# MultiPSU.net
KiCad netlist of a schematic drawn in EAGLE
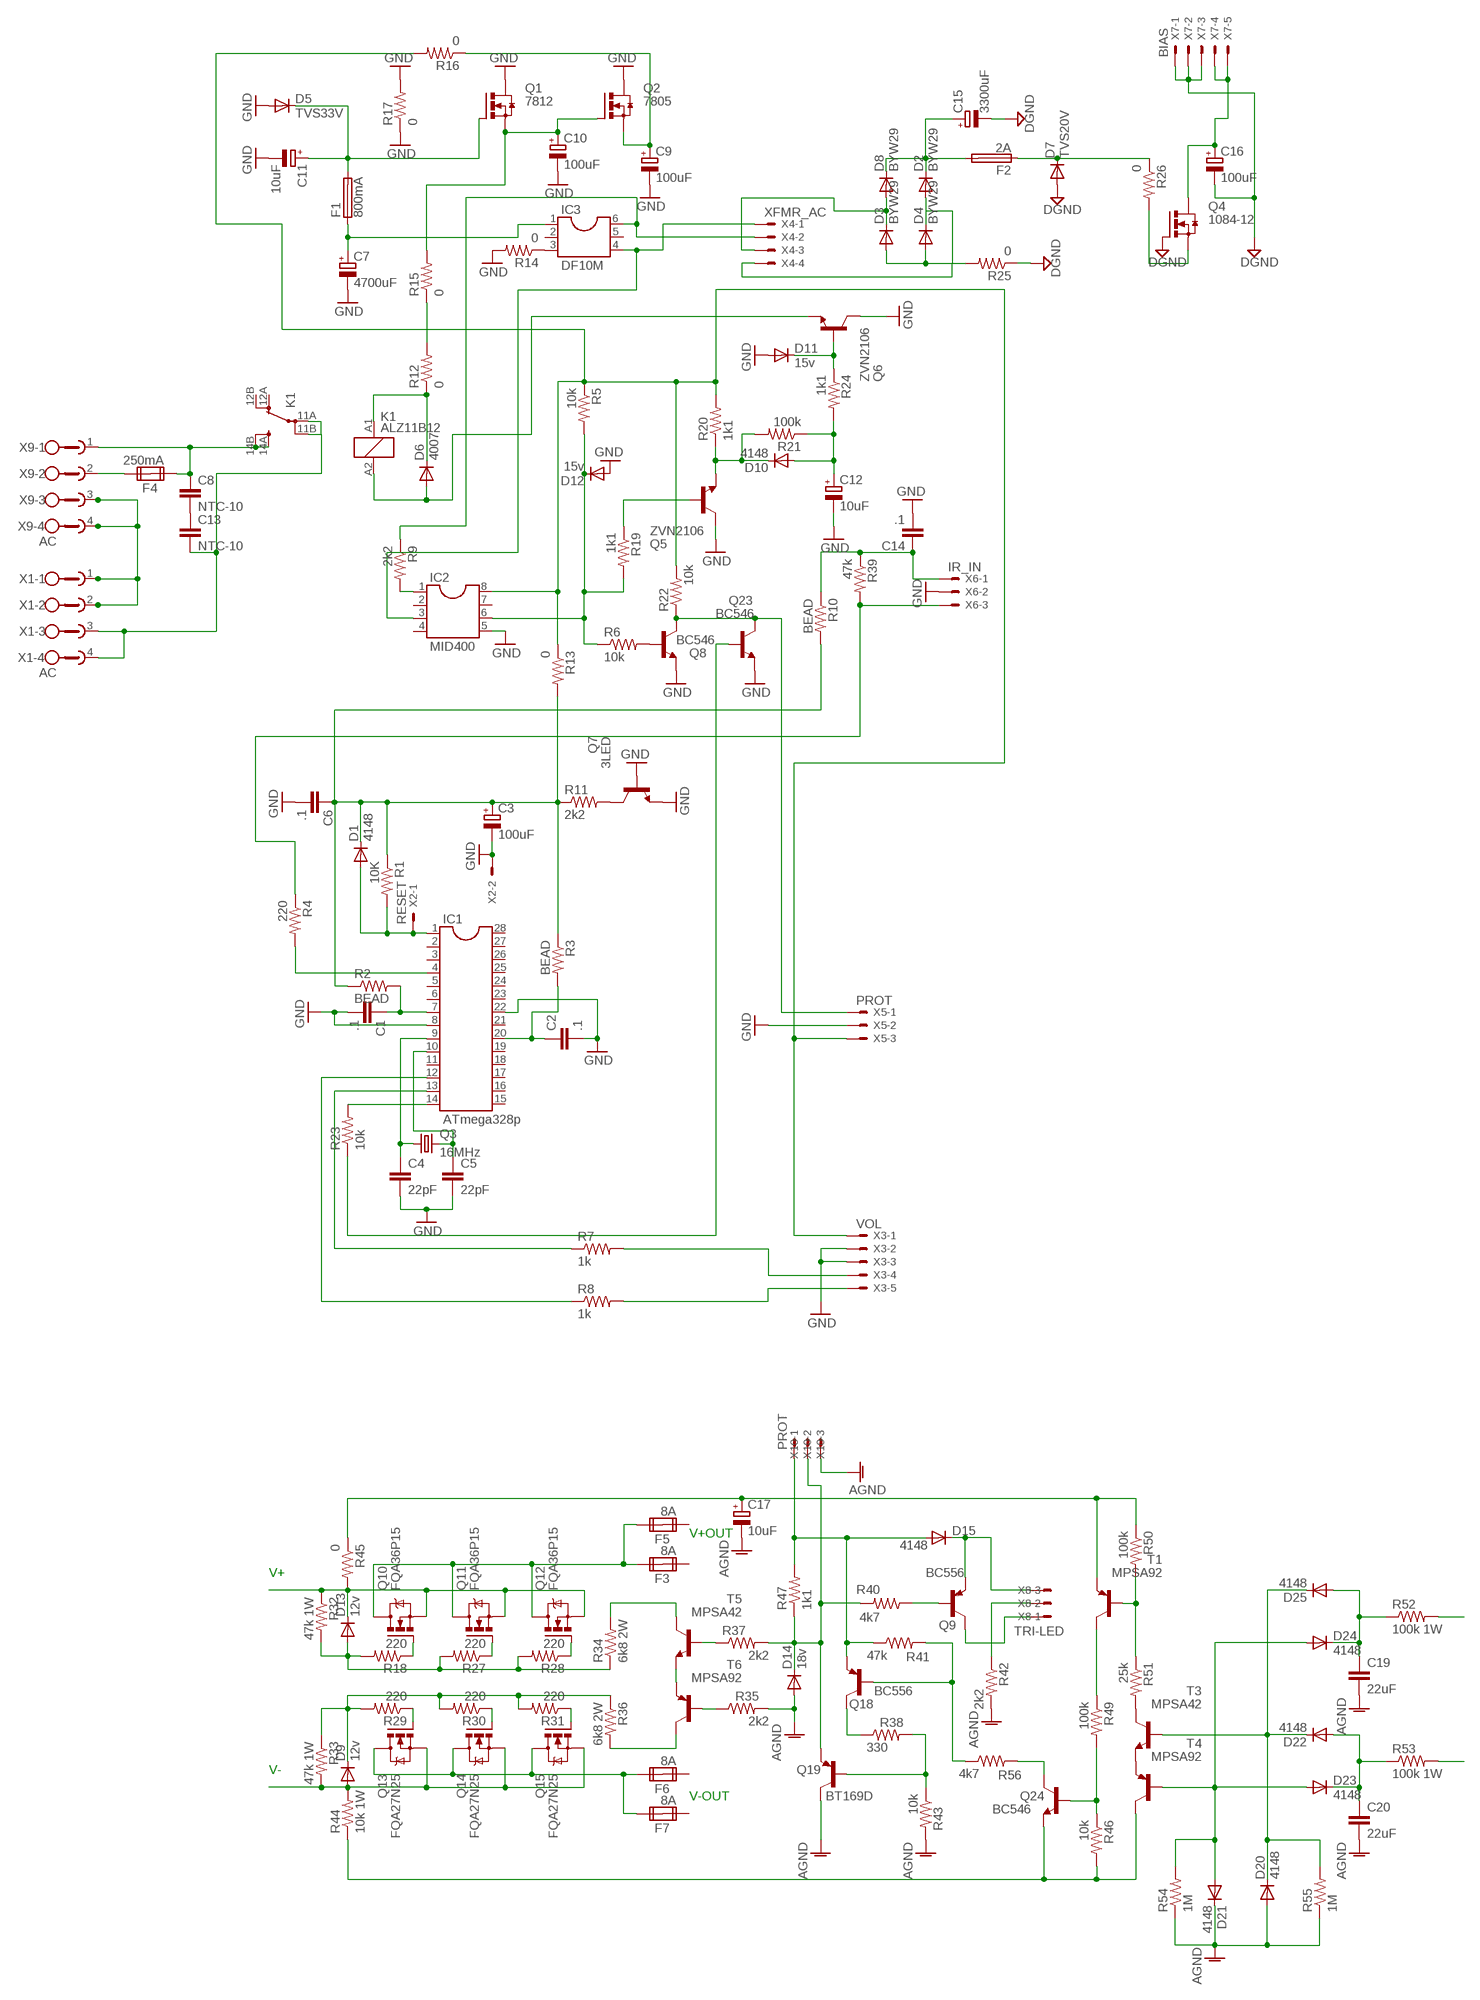
[diagram p0: schematic, sheet 1]

(export (version "E")
  (design (tool "Eeschema 10.0.6"))
  (components
    (comp (ref "C1")
      (value ".1")
      (footprint "eagle-import:C1210K")
      (libsource (lib "eagle-import") (part "C-EUC1210K"))
    )
    (comp (ref "C2")
      (value ".1")
      (footprint "eagle-import:C1210K")
      (libsource (lib "eagle-import") (part "C-EUC1210K"))
    )
    (comp (ref "C3")
      (value "100uF")
      (footprint "eagle-import:E3,5-10")
      (libsource (lib "eagle-import") (part "CPOL-EUE3.5-10"))
    )
    (comp (ref "C4")
      (value "22pF")
      (footprint "eagle-import:C1210K")
      (libsource (lib "eagle-import") (part "C-EUC1210K"))
    )
    (comp (ref "C5")
      (value "22pF")
      (footprint "eagle-import:C1210K")
      (libsource (lib "eagle-import") (part "C-EUC1210K"))
    )
    (comp (ref "C6")
      (value ".1")
      (footprint "eagle-import:C1210K")
      (libsource (lib "eagle-import") (part "C-EUC1210K"))
    )
    (comp (ref "C7")
      (value "4700uF")
      (footprint "eagle-import:E7,5-16")
      (libsource (lib "eagle-import") (part "CPOL-EUE7.5-16"))
    )
    (comp (ref "C8")
      (value "NTC-10")
      (footprint "eagle-import:C102-054X133")
      (libsource (lib "eagle-import") (part "C-EU102-054X133"))
    )
    (comp (ref "C9")
      (value "100uF")
      (footprint "eagle-import:E3,5-10")
      (libsource (lib "eagle-import") (part "CPOL-EUE3.5-10"))
    )
    (comp (ref "C10")
      (value "100uF")
      (footprint "eagle-import:E3,5-10")
      (libsource (lib "eagle-import") (part "CPOL-EUE3.5-10"))
    )
    (comp (ref "C11")
      (value "10uF")
      (footprint "eagle-import:E3,5-10")
      (libsource (lib "eagle-import") (part "CPOL-EUE3.5-10"))
    )
    (comp (ref "C12")
      (value "10uF")
      (footprint "eagle-import:E3,5-10")
      (libsource (lib "eagle-import") (part "CPOL-EUE3.5-10"))
    )
    (comp (ref "C13")
      (value "NTC-10")
      (footprint "eagle-import:C102-054X133")
      (libsource (lib "eagle-import") (part "C-EU102-054X133"))
    )
    (comp (ref "C14")
      (value ".1")
      (footprint "eagle-import:C1210K")
      (libsource (lib "eagle-import") (part "C-EUC1210K"))
    )
    (comp (ref "C15")
      (value "3300uF")
      (footprint "eagle-import:E7,5-16")
      (libsource (lib "eagle-import") (part "CPOL-EUE7.5-16"))
    )
    (comp (ref "C16")
      (value "100uF")
      (footprint "eagle-import:E3,5-10")
      (libsource (lib "eagle-import") (part "CPOL-EUE3.5-10"))
    )
    (comp (ref "C17")
      (value "10uF")
      (footprint "eagle-import:E3,5-10")
      (libsource (lib "eagle-import") (part "CPOL-EUE3.5-10"))
    )
    (comp (ref "C19")
      (value "22uF")
      (footprint "eagle-import:C050-075X075")
      (libsource (lib "eagle-import") (part "C-EU050-075X075"))
    )
    (comp (ref "C20")
      (value "22uF")
      (footprint "eagle-import:C050-075X075")
      (libsource (lib "eagle-import") (part "C-EU050-075X075"))
    )
    (comp (ref "D1")
      (value "4148")
      (footprint "eagle-import:DO35-7")
      (libsource (lib "eagle-import") (part "1N4148DO35-7"))
    )
    (comp (ref "D2")
      (value "BYW29")
      (footprint "eagle-import:DO220S")
      (libsource (lib "eagle-import") (part "BYW29"))
    )
    (comp (ref "D3")
      (value "BYW29")
      (footprint "eagle-import:DO220S")
      (libsource (lib "eagle-import") (part "BYW29"))
    )
    (comp (ref "D4")
      (value "BYW29")
      (footprint "eagle-import:DO220S")
      (libsource (lib "eagle-import") (part "BYW29"))
    )
    (comp (ref "D5")
      (value "TVS33V")
      (footprint "eagle-import:SOD57-10")
      (libsource (lib "eagle-import") (part "BY448"))
    )
    (comp (ref "D6")
      (value "4007")
      (footprint "eagle-import:DO41-10")
      (libsource (lib "eagle-import") (part "1N4004"))
    )
    (comp (ref "D7")
      (value "TVS20V")
      (footprint "eagle-import:SOD57-10")
      (libsource (lib "eagle-import") (part "BY448"))
    )
    (comp (ref "D8")
      (value "BYW29")
      (footprint "eagle-import:DO220S")
      (libsource (lib "eagle-import") (part "BYW29"))
    )
    (comp (ref "D9")
      (value "12v")
      (footprint "eagle-import:DO41-10")
      (libsource (lib "eagle-import") (part "1N4004"))
    )
    (comp (ref "D10")
      (value "4148")
      (footprint "eagle-import:DO35-10")
      (libsource (lib "eagle-import") (part "1N4148DO35-10"))
    )
    (comp (ref "D11")
      (value "15v")
      (footprint "eagle-import:DO35-7")
      (libsource (lib "eagle-import") (part "1N4148DO35-7"))
    )
    (comp (ref "D12")
      (value "15v")
      (footprint "eagle-import:DO35-7")
      (libsource (lib "eagle-import") (part "1N4148DO35-7"))
    )
    (comp (ref "D13")
      (value "12v")
      (footprint "eagle-import:DO41-10")
      (libsource (lib "eagle-import") (part "1N4004"))
    )
    (comp (ref "D14")
      (value "18v")
      (footprint "eagle-import:DO41-10")
      (libsource (lib "eagle-import") (part "1N4004"))
    )
    (comp (ref "D15")
      (value "4148")
      (footprint "eagle-import:DO41-10")
      (libsource (lib "eagle-import") (part "1N4004"))
    )
    (comp (ref "D20")
      (value "4148")
      (footprint "eagle-import:DO35-7")
      (libsource (lib "eagle-import") (part "1N4148DO35-7"))
    )
    (comp (ref "D21")
      (value "4148")
      (footprint "eagle-import:DO35-7")
      (libsource (lib "eagle-import") (part "1N4148DO35-7"))
    )
    (comp (ref "D22")
      (value "4148")
      (footprint "eagle-import:DO35-7")
      (libsource (lib "eagle-import") (part "1N4148DO35-7"))
    )
    (comp (ref "D23")
      (value "4148")
      (footprint "eagle-import:DO35-7")
      (libsource (lib "eagle-import") (part "1N4148DO35-7"))
    )
    (comp (ref "D24")
      (value "4148")
      (footprint "eagle-import:DO35-7")
      (libsource (lib "eagle-import") (part "1N4148DO35-7"))
    )
    (comp (ref "D25")
      (value "4148")
      (footprint "eagle-import:DO35-7")
      (libsource (lib "eagle-import") (part "1N4148DO35-7"))
    )
    (comp (ref "F1")
      (value "800mA")
      (footprint "eagle-import:19560")
      (fields (field (name "MPN") "56000001009"))
      (libsource (lib "eagle-import") (part "19560"))
    )
    (comp (ref "F2")
      (value "2A")
      (footprint "eagle-import:19560")
      (fields (field (name "MPN") "56000001009"))
      (libsource (lib "eagle-import") (part "19560"))
    )
    (comp (ref "F3")
      (value "8A")
      (footprint "eagle-import:FUSE1")
      (libsource (lib "eagle-import") (part "FUSE2P"))
    )
    (comp (ref "F4")
      (value "250mA")
      (footprint "eagle-import:FUSE1")
      (libsource (lib "eagle-import") (part "FUSE2P"))
    )
    (comp (ref "F5")
      (value "8A")
      (footprint "eagle-import:FUSE1")
      (libsource (lib "eagle-import") (part "FUSE2P"))
    )
    (comp (ref "F6")
      (value "8A")
      (footprint "eagle-import:FUSE1")
      (libsource (lib "eagle-import") (part "FUSE2P"))
    )
    (comp (ref "F7")
      (value "8A")
      (footprint "eagle-import:FUSE1")
      (libsource (lib "eagle-import") (part "FUSE2P"))
    )
    (comp (ref "IC1")
      (value "ATmega328p")
      (footprint "eagle-import:DIL28-3")
      (libsource (lib "eagle-import") (part "DIL28-3"))
    )
    (comp (ref "IC2")
      (value "MID400")
      (footprint "eagle-import:DIL08")
      (libsource (lib "eagle-import") (part "DIL8"))
    )
    (comp (ref "IC3")
      (value "DF10M")
      (footprint "eagle-import:DIL06")
      (libsource (lib "eagle-import") (part "DIL6"))
    )
    (comp (ref "K1")
      (value "ALZ11B12")
      (footprint "eagle-import:RT-C_O16A5")
      (fields (field (name "MPN") "RT314730"))
      (libsource (lib "eagle-import") (part "RT314730"))
    )
    (comp (ref "Q1")
      (value "7812")
      (footprint "eagle-import:TO220BH")
      (libsource (lib "eagle-import") (part "IRFI540NPBF"))
    )
    (comp (ref "Q2")
      (value "7805")
      (footprint "eagle-import:TO220BH")
      (libsource (lib "eagle-import") (part "IRFI540NPBF"))
    )
    (comp (ref "Q3")
      (value "16MHz")
      (footprint "eagle-import:HC49_S")
      (libsource (lib "eagle-import") (part "CRYSTALHC49S"))
    )
    (comp (ref "Q4")
      (value "1084-12")
      (footprint "eagle-import:TO220BH")
      (libsource (lib "eagle-import") (part "IRFI540NPBF"))
    )
    (comp (ref "Q5")
      (value "ZVN2106")
      (footprint "eagle-import:TO92-EBC")
      (libsource (lib "eagle-import") (part "BC550B"))
    )
    (comp (ref "Q6")
      (value "ZVN2106")
      (footprint "eagle-import:TO92-EBC")
      (libsource (lib "eagle-import") (part "BC550B"))
    )
    (comp (ref "Q7")
      (value "3LED")
      (footprint "eagle-import:TO92-EBC")
      (libsource (lib "eagle-import") (part "BC546A"))
    )
    (comp (ref "Q8")
      (value "BC546")
      (footprint "eagle-import:TO92-EBC")
      (libsource (lib "eagle-import") (part "BC550B"))
    )
    (comp (ref "Q9")
      (value "BC556")
      (footprint "eagle-import:TO92-EBC")
      (libsource (lib "eagle-import") (part "BC560"))
    )
    (comp (ref "Q10")
      (value "FQA36P15")
      (footprint "eagle-import:TO-247AD-H")
      (libsource (lib "eagle-import") (part "IXF?6NH_100"))
    )
    (comp (ref "Q11")
      (value "FQA36P15")
      (footprint "eagle-import:TO-247AD-H")
      (libsource (lib "eagle-import") (part "IXF?6NH_100"))
    )
    (comp (ref "Q12")
      (value "FQA36P15")
      (footprint "eagle-import:TO-247AD-H")
      (libsource (lib "eagle-import") (part "IXF?6NH_100"))
    )
    (comp (ref "Q13")
      (value "FQA27N25")
      (footprint "eagle-import:TO-247AD-H")
      (libsource (lib "eagle-import") (part "IXF?6NH_100"))
    )
    (comp (ref "Q14")
      (value "FQA27N25")
      (footprint "eagle-import:TO-247AD-H")
      (libsource (lib "eagle-import") (part "IXF?6NH_100"))
    )
    (comp (ref "Q15")
      (value "FQA27N25")
      (footprint "eagle-import:TO-247AD-H")
      (libsource (lib "eagle-import") (part "IXF?6NH_100"))
    )
    (comp (ref "Q18")
      (value "BC556")
      (footprint "eagle-import:TO92-EBC")
      (libsource (lib "eagle-import") (part "BC560"))
    )
    (comp (ref "Q19")
      (value "BT169D")
      (footprint "eagle-import:TO92-EBC")
      (libsource (lib "eagle-import") (part "BC560"))
    )
    (comp (ref "Q23")
      (value "BC546")
      (footprint "eagle-import:TO92-EBC")
      (libsource (lib "eagle-import") (part "BC550B"))
    )
    (comp (ref "Q24")
      (value "BC546")
      (footprint "eagle-import:TO92-EBC")
      (libsource (lib "eagle-import") (part "BC550B"))
    )
    (comp (ref "R1")
      (value "10K")
      (footprint "eagle-import:0309_10")
      (libsource (lib "eagle-import") (part "R-US_0309/10"))
    )
    (comp (ref "R2")
      (value "BEAD")
      (footprint "eagle-import:0309_10")
      (libsource (lib "eagle-import") (part "R-US_0309/10"))
    )
    (comp (ref "R3")
      (value "BEAD")
      (footprint "eagle-import:0309_12")
      (libsource (lib "eagle-import") (part "R-US_0309/12"))
    )
    (comp (ref "R4")
      (value "220")
      (footprint "eagle-import:0309_12")
      (libsource (lib "eagle-import") (part "R-US_0309/12"))
    )
    (comp (ref "R5")
      (value "10k")
      (footprint "eagle-import:0309_10")
      (libsource (lib "eagle-import") (part "R-US_0309/10"))
    )
    (comp (ref "R6")
      (value "10k")
      (footprint "eagle-import:0309_12")
      (libsource (lib "eagle-import") (part "R-US_0309/12"))
    )
    (comp (ref "R7")
      (value "1k")
      (footprint "eagle-import:R1210")
      (libsource (lib "eagle-import") (part "R-US_R1210"))
    )
    (comp (ref "R8")
      (value "1k")
      (footprint "eagle-import:R1210")
      (libsource (lib "eagle-import") (part "R-US_R1210"))
    )
    (comp (ref "R9")
      (value "2k2")
      (footprint "eagle-import:0309_12")
      (libsource (lib "eagle-import") (part "R-US_0309/12"))
    )
    (comp (ref "R10")
      (value "BEAD")
      (footprint "eagle-import:0309_10")
      (libsource (lib "eagle-import") (part "R-US_0309/10"))
    )
    (comp (ref "R11")
      (value "2k2")
      (footprint "eagle-import:0309_10")
      (libsource (lib "eagle-import") (part "R-US_0309/10"))
    )
    (comp (ref "R12")
      (value "0")
      (footprint "eagle-import:0309_10")
      (libsource (lib "eagle-import") (part "R-US_0309/10"))
    )
    (comp (ref "R13")
      (value "0")
      (footprint "eagle-import:0309_12")
      (libsource (lib "eagle-import") (part "R-US_0309/12"))
    )
    (comp (ref "R14")
      (value "0")
      (footprint "eagle-import:0309_10")
      (libsource (lib "eagle-import") (part "R-US_0309/10"))
    )
    (comp (ref "R15")
      (value "0")
      (footprint "eagle-import:0309_12")
      (libsource (lib "eagle-import") (part "R-US_0309/12"))
    )
    (comp (ref "R16")
      (value "0")
      (footprint "eagle-import:0309_12")
      (libsource (lib "eagle-import") (part "R-US_0309/12"))
    )
    (comp (ref "R17")
      (value "0")
      (footprint "eagle-import:0309_12")
      (libsource (lib "eagle-import") (part "R-US_0309/12"))
    )
    (comp (ref "R18")
      (value "220")
      (footprint "eagle-import:0309_12")
      (libsource (lib "eagle-import") (part "R-US_0309/12"))
    )
    (comp (ref "R19")
      (value "1k1")
      (footprint "eagle-import:0309_12")
      (libsource (lib "eagle-import") (part "R-US_0309/12"))
    )
    (comp (ref "R20")
      (value "1k1")
      (footprint "eagle-import:0309_10")
      (libsource (lib "eagle-import") (part "R-US_0309/10"))
    )
    (comp (ref "R21")
      (value "100k")
      (footprint "eagle-import:0309_10")
      (libsource (lib "eagle-import") (part "R-US_0309/10"))
    )
    (comp (ref "R22")
      (value "10k")
      (footprint "eagle-import:0309_10")
      (libsource (lib "eagle-import") (part "R-US_0309/10"))
    )
    (comp (ref "R23")
      (value "10k")
      (footprint "eagle-import:R1210")
      (libsource (lib "eagle-import") (part "R-US_R1210"))
    )
    (comp (ref "R24")
      (value "1k1")
      (footprint "eagle-import:0309_10")
      (libsource (lib "eagle-import") (part "R-US_0309/10"))
    )
    (comp (ref "R25")
      (value "0")
      (footprint "eagle-import:0309_12")
      (libsource (lib "eagle-import") (part "R-US_0309/12"))
    )
    (comp (ref "R26")
      (value "0")
      (footprint "eagle-import:0309_12")
      (libsource (lib "eagle-import") (part "R-US_0309/12"))
    )
    (comp (ref "R27")
      (value "220")
      (footprint "eagle-import:0309_12")
      (libsource (lib "eagle-import") (part "R-US_0309/12"))
    )
    (comp (ref "R28")
      (value "220")
      (footprint "eagle-import:0309_12")
      (libsource (lib "eagle-import") (part "R-US_0309/12"))
    )
    (comp (ref "R29")
      (value "220")
      (footprint "eagle-import:0309_12")
      (libsource (lib "eagle-import") (part "R-US_0309/12"))
    )
    (comp (ref "R30")
      (value "220")
      (footprint "eagle-import:0309_12")
      (libsource (lib "eagle-import") (part "R-US_0309/12"))
    )
    (comp (ref "R31")
      (value "220")
      (footprint "eagle-import:0309_12")
      (libsource (lib "eagle-import") (part "R-US_0309/12"))
    )
    (comp (ref "R32")
      (value "47k 1W")
      (footprint "eagle-import:0411_15")
      (libsource (lib "eagle-import") (part "R-US_0411/15"))
    )
    (comp (ref "R33")
      (value "47k 1W")
      (footprint "eagle-import:0411_15")
      (libsource (lib "eagle-import") (part "R-US_0411/15"))
    )
    (comp (ref "R34")
      (value "6k8 2W")
      (footprint "eagle-import:0411_15")
      (libsource (lib "eagle-import") (part "R-US_0411/15"))
    )
    (comp (ref "R35")
      (value "2k2")
      (footprint "eagle-import:0309_10")
      (libsource (lib "eagle-import") (part "R-US_0309/10"))
    )
    (comp (ref "R36")
      (value "6k8 2W")
      (footprint "eagle-import:0411_15")
      (libsource (lib "eagle-import") (part "R-US_0411/15"))
    )
    (comp (ref "R37")
      (value "2k2")
      (footprint "eagle-import:0309_10")
      (libsource (lib "eagle-import") (part "R-US_0309/10"))
    )
    (comp (ref "R38")
      (value "330")
      (footprint "eagle-import:0309_10")
      (libsource (lib "eagle-import") (part "R-US_0309/10"))
    )
    (comp (ref "R39")
      (value "47k")
      (footprint "eagle-import:0309_10")
      (libsource (lib "eagle-import") (part "R-US_0309/10"))
    )
    (comp (ref "R40")
      (value "4k7")
      (footprint "eagle-import:0309_10")
      (libsource (lib "eagle-import") (part "R-US_0309/10"))
    )
    (comp (ref "R41")
      (value "47k")
      (footprint "eagle-import:0309_10")
      (libsource (lib "eagle-import") (part "R-US_0309/10"))
    )
    (comp (ref "R42")
      (value "2k2")
      (footprint "eagle-import:0309_10")
      (libsource (lib "eagle-import") (part "R-US_0309/10"))
    )
    (comp (ref "R43")
      (value "10k")
      (footprint "eagle-import:0309_10")
      (libsource (lib "eagle-import") (part "R-US_0309/10"))
    )
    (comp (ref "R44")
      (value "10k 1W")
      (footprint "eagle-import:0411_15")
      (libsource (lib "eagle-import") (part "R-US_0411/15"))
    )
    (comp (ref "R45")
      (value "0")
      (footprint "eagle-import:0309_12")
      (libsource (lib "eagle-import") (part "R-US_0309/12"))
    )
    (comp (ref "R46")
      (value "10k")
      (footprint "eagle-import:0411_15")
      (libsource (lib "eagle-import") (part "R-US_0411/15"))
    )
    (comp (ref "R47")
      (value "1k1")
      (footprint "eagle-import:0309_10")
      (libsource (lib "eagle-import") (part "R-US_0309/10"))
    )
    (comp (ref "R49")
      (value "100k")
      (footprint "eagle-import:0411_15")
      (libsource (lib "eagle-import") (part "R-US_0411/15"))
    )
    (comp (ref "R50")
      (value "100k")
      (footprint "eagle-import:0309_10")
      (libsource (lib "eagle-import") (part "R-US_0309/10"))
    )
    (comp (ref "R51")
      (value "25k")
      (footprint "eagle-import:0309_10")
      (libsource (lib "eagle-import") (part "R-US_0309/10"))
    )
    (comp (ref "R52")
      (value "100k 1W")
      (footprint "eagle-import:0309_10")
      (libsource (lib "eagle-import") (part "R-US_0309/10"))
    )
    (comp (ref "R53")
      (value "100k 1W")
      (footprint "eagle-import:0309_10")
      (libsource (lib "eagle-import") (part "R-US_0309/10"))
    )
    (comp (ref "R54")
      (value "1M")
      (footprint "eagle-import:R1210")
      (libsource (lib "eagle-import") (part "R-US_R1210"))
    )
    (comp (ref "R55")
      (value "1M")
      (footprint "eagle-import:R1210")
      (libsource (lib "eagle-import") (part "R-US_R1210"))
    )
    (comp (ref "R56")
      (value "4k7")
      (footprint "eagle-import:0309_10")
      (libsource (lib "eagle-import") (part "R-US_0309/10"))
    )
    (comp (ref "T1")
      (value "MPSA92")
      (footprint "eagle-import:TO92-EBC")
      (libsource (lib "eagle-import") (part "-PNP-TO92-EBCMPSA92"))
    )
    (comp (ref "T3")
      (value "MPSA42")
      (footprint "eagle-import:TO92-EBC")
      (libsource (lib "eagle-import") (part "-NPN-TO92-EBCMPSA42"))
    )
    (comp (ref "T4")
      (value "MPSA92")
      (footprint "eagle-import:TO92-EBC")
      (libsource (lib "eagle-import") (part "-PNP-TO92-EBCMPSA92"))
    )
    (comp (ref "T5")
      (value "MPSA42")
      (footprint "eagle-import:TO92-EBC")
      (libsource (lib "eagle-import") (part "-NPN-TO92-EBCMPSA42"))
    )
    (comp (ref "T6")
      (value "MPSA92")
      (footprint "eagle-import:TO92-EBC")
      (libsource (lib "eagle-import") (part "-PNP-TO92-EBCMPSA92"))
    )
    (comp (ref "X1")
      (value "AC")
      (footprint "eagle-import:GMSTBA4")
      (fields (field (name "MF") "FARNELL") (field (name "MPN") "1757268"))
      (libsource (lib "eagle-import") (part "GMSTBA4"))
    )
    (comp (ref "X2")
      (value "RESET")
      (footprint "eagle-import:22-23-2021")
      (fields (field (name "MF") "MOLEX") (field (name "MPN") "22-23-2021"))
      (libsource (lib "eagle-import") (part "22-23-2021"))
    )
    (comp (ref "X3")
      (value "VOL")
      (footprint "eagle-import:22-23-2051")
      (fields (field (name "MF") "MOLEX") (field (name "MPN") "22-23-2051"))
      (libsource (lib "eagle-import") (part "22-23-2051"))
    )
    (comp (ref "X4")
      (value "XFMR_AC")
      (footprint "eagle-import:5566-4")
      (libsource (lib "eagle-import") (part "5566-4"))
    )
    (comp (ref "X5")
      (value "PROT")
      (footprint "eagle-import:22-23-2031")
      (fields (field (name "MF") "MOLEX") (field (name "MPN") "22-23-2031"))
      (libsource (lib "eagle-import") (part "22-23-2031"))
    )
    (comp (ref "X6")
      (value "IR_IN")
      (footprint "eagle-import:22-23-2031")
      (fields (field (name "MF") "MOLEX") (field (name "MPN") "22-23-2031"))
      (libsource (lib "eagle-import") (part "22-23-2031"))
    )
    (comp (ref "X7")
      (value "BIAS")
      (footprint "eagle-import:22-23-2051")
      (fields (field (name "MF") "MOLEX") (field (name "MPN") "22-23-2051"))
      (libsource (lib "eagle-import") (part "22-23-2051"))
    )
    (comp (ref "X8")
      (value "TRI-LED")
      (footprint "eagle-import:22-23-2031")
      (fields (field (name "MF") "MOLEX") (field (name "MPN") "22-23-2031"))
      (libsource (lib "eagle-import") (part "22-23-2031"))
    )
    (comp (ref "X9")
      (value "AC")
      (footprint "eagle-import:GMSTBA4")
      (fields (field (name "MF") "FARNELL") (field (name "MPN") "1757268"))
      (libsource (lib "eagle-import") (part "GMSTBA4"))
    )
    (comp (ref "X10")
      (value "PROT")
      (footprint "eagle-import:22-23-2031")
      (fields (field (name "MF") "MOLEX") (field (name "MPN") "22-23-2031"))
      (libsource (lib "eagle-import") (part "22-23-2031"))
    )
  )
  (nets
    (net (code "1") (name "AGND") (class "Default")
      (node (ref "C17") (pin "-") (pinfunction "-_-") (pintype "passive"))
      (node (ref "C19") (pin "2") (pinfunction "2_2") (pintype "passive"))
      (node (ref "C20") (pin "2") (pinfunction "2_2") (pintype "passive"))
      (node (ref "D14") (pin "A") (pinfunction "A_A") (pintype "passive"))
      (node (ref "D20") (pin "A") (pinfunction "A_A") (pintype "passive"))
      (node (ref "D21") (pin "C") (pinfunction "C_C") (pintype "passive"))
      (node (ref "Q19") (pin "C") (pinfunction "C_C") (pintype "passive"))
      (node (ref "R35") (pin "2") (pinfunction "2_2") (pintype "passive"))
      (node (ref "R42") (pin "2") (pinfunction "2_2") (pintype "passive"))
      (node (ref "R43") (pin "2") (pinfunction "2_2") (pintype "passive"))
      (node (ref "R54") (pin "1") (pinfunction "1_1") (pintype "passive"))
      (node (ref "R55") (pin "1") (pinfunction "1_1") (pintype "passive"))
      (node (ref "X10") (pin "3") (pinfunction "S_3") (pintype "passive"))
    )
    (net (code "2") (name "DGND") (class "Default")
      (node (ref "C15") (pin "-") (pinfunction "-_-") (pintype "passive"))
      (node (ref "C16") (pin "-") (pinfunction "-_-") (pintype "passive"))
      (node (ref "D7") (pin "A") (pinfunction "A_A") (pintype "passive"))
      (node (ref "Q4") (pin "G") (pinfunction "G_G") (pintype "passive"))
      (node (ref "R25") (pin "1") (pinfunction "1_1") (pintype "passive"))
      (node (ref "X7") (pin "1") (pinfunction "S_1") (pintype "passive"))
      (node (ref "X7") (pin "2") (pinfunction "S_2") (pintype "passive"))
      (node (ref "X7") (pin "3") (pinfunction "S_3") (pintype "passive"))
    )
    (net (code "3") (name "GND") (class "Default")
      (node (ref "C1") (pin "2") (pinfunction "2_2") (pintype "passive"))
      (node (ref "C10") (pin "-") (pinfunction "-_-") (pintype "passive"))
      (node (ref "C11") (pin "-") (pinfunction "-_-") (pintype "passive"))
      (node (ref "C12") (pin "-") (pinfunction "-_-") (pintype "passive"))
      (node (ref "C14") (pin "2") (pinfunction "2_2") (pintype "passive"))
      (node (ref "C2") (pin "2") (pinfunction "2_2") (pintype "passive"))
      (node (ref "C3") (pin "-") (pinfunction "-_-") (pintype "passive"))
      (node (ref "C4") (pin "2") (pinfunction "2_2") (pintype "passive"))
      (node (ref "C5") (pin "2") (pinfunction "2_2") (pintype "passive"))
      (node (ref "C6") (pin "2") (pinfunction "2_2") (pintype "passive"))
      (node (ref "C7") (pin "-") (pinfunction "-_-") (pintype "passive"))
      (node (ref "C9") (pin "-") (pinfunction "-_-") (pintype "passive"))
      (node (ref "D11") (pin "A") (pinfunction "A_A") (pintype "passive"))
      (node (ref "D12") (pin "A") (pinfunction "A_A") (pintype "passive"))
      (node (ref "D5") (pin "A") (pinfunction "A_A") (pintype "passive"))
      (node (ref "IC1") (pin "22") (pinfunction "22_22") (pintype "passive"))
      (node (ref "IC1") (pin "8") (pinfunction "8_8") (pintype "passive"))
      (node (ref "IC2") (pin "5") (pinfunction "5_5") (pintype "passive"))
      (node (ref "Q1") (pin "D") (pinfunction "D_D") (pintype "passive"))
      (node (ref "Q2") (pin "D") (pinfunction "D_D") (pintype "passive"))
      (node (ref "Q23") (pin "E") (pinfunction "E_E") (pintype "passive"))
      (node (ref "Q5") (pin "C") (pinfunction "C_C") (pintype "passive"))
      (node (ref "Q6") (pin "C") (pinfunction "C_C") (pintype "passive"))
      (node (ref "Q7") (pin "B") (pinfunction "B_B") (pintype "passive"))
      (node (ref "Q7") (pin "E") (pinfunction "E_E") (pintype "passive"))
      (node (ref "Q8") (pin "E") (pinfunction "E_E") (pintype "passive"))
      (node (ref "R14") (pin "2") (pinfunction "2_2") (pintype "passive"))
      (node (ref "R17") (pin "1") (pinfunction "1_1") (pintype "passive"))
      (node (ref "R17") (pin "2") (pinfunction "2_2") (pintype "passive"))
      (node (ref "X2") (pin "2") (pinfunction "S_2") (pintype "passive"))
      (node (ref "X3") (pin "2") (pinfunction "S_2") (pintype "passive"))
      (node (ref "X3") (pin "3") (pinfunction "S_3") (pintype "passive"))
      (node (ref "X5") (pin "2") (pinfunction "S_2") (pintype "passive"))
      (node (ref "X6") (pin "2") (pinfunction "S_2") (pintype "passive"))
    )
    (net (code "4") (name "Net-(C1-Pad1)") (class "Default")
      (node (ref "C1") (pin "1") (pinfunction "1_1") (pintype "passive"))
      (node (ref "IC1") (pin "7") (pinfunction "7_7") (pintype "passive"))
      (node (ref "R2") (pin "2") (pinfunction "2_2") (pintype "passive"))
    )
    (net (code "5") (name "Net-(C2-Pad1)") (class "Default")
      (node (ref "C2") (pin "1") (pinfunction "1_1") (pintype "passive"))
      (node (ref "IC1") (pin "20") (pinfunction "20_20") (pintype "passive"))
      (node (ref "R3") (pin "2") (pinfunction "2_2") (pintype "passive"))
    )
    (net (code "6") (name "Net-(C3-Pad+)") (class "Default")
      (node (ref "C3") (pin "+") (pinfunction "+_+") (pintype "passive"))
      (node (ref "C6") (pin "1") (pinfunction "1_1") (pintype "passive"))
      (node (ref "D1") (pin "C") (pinfunction "C_C") (pintype "passive"))
      (node (ref "R1") (pin "1") (pinfunction "1_1") (pintype "passive"))
      (node (ref "R10") (pin "2") (pinfunction "2_2") (pintype "passive"))
      (node (ref "R11") (pin "1") (pinfunction "1_1") (pintype "passive"))
      (node (ref "R13") (pin "2") (pinfunction "2_2") (pintype "passive"))
      (node (ref "R2") (pin "1") (pinfunction "1_1") (pintype "passive"))
      (node (ref "R3") (pin "1") (pinfunction "1_1") (pintype "passive"))
    )
    (net (code "7") (name "Net-(C4-Pad1)") (class "Default")
      (node (ref "C4") (pin "1") (pinfunction "1_1") (pintype "passive"))
      (node (ref "IC1") (pin "9") (pinfunction "9_9") (pintype "passive"))
      (node (ref "Q3") (pin "1") (pinfunction "1_1") (pintype "passive"))
    )
    (net (code "8") (name "Net-(C5-Pad1)") (class "Default")
      (node (ref "C5") (pin "1") (pinfunction "1_1") (pintype "passive"))
      (node (ref "IC1") (pin "10") (pinfunction "10_10") (pintype "passive"))
      (node (ref "Q3") (pin "2") (pinfunction "2_2") (pintype "passive"))
    )
    (net (code "9") (name "Net-(C7-Pad+)") (class "Default")
      (node (ref "C7") (pin "+") (pinfunction "+_+") (pintype "passive"))
      (node (ref "F1") (pin "1") (pinfunction "1_1") (pintype "passive"))
      (node (ref "IC3") (pin "1") (pinfunction "1_1") (pintype "passive"))
    )
    (net (code "10") (name "Net-(C9-Pad+)") (class "Default")
      (node (ref "C9") (pin "+") (pinfunction "+_+") (pintype "passive"))
      (node (ref "Q2") (pin "S") (pinfunction "S_S") (pintype "passive"))
      (node (ref "R16") (pin "1") (pinfunction "1_1") (pintype "passive"))
    )
    (net (code "11") (name "Net-(C10-Pad+)") (class "Default")
      (node (ref "C10") (pin "+") (pinfunction "+_+") (pintype "passive"))
      (node (ref "Q1") (pin "S") (pinfunction "S_S") (pintype "passive"))
      (node (ref "Q2") (pin "G") (pinfunction "G_G") (pintype "passive"))
      (node (ref "R15") (pin "2") (pinfunction "2_2") (pintype "passive"))
    )
    (net (code "12") (name "Net-(C11-Pad+)") (class "Default")
      (node (ref "C11") (pin "+") (pinfunction "+_+") (pintype "passive"))
      (node (ref "D5") (pin "C") (pinfunction "C_C") (pintype "passive"))
      (node (ref "F1") (pin "2") (pinfunction "2_2") (pintype "passive"))
      (node (ref "Q1") (pin "G") (pinfunction "G_G") (pintype "passive"))
    )
    (net (code "13") (name "Net-(C12-Pad+)") (class "Default")
      (node (ref "C12") (pin "+") (pinfunction "+_+") (pintype "passive"))
      (node (ref "D10") (pin "A") (pinfunction "A_A") (pintype "passive"))
      (node (ref "R21") (pin "1") (pinfunction "1_1") (pintype "passive"))
      (node (ref "R24") (pin "2") (pinfunction "2_2") (pintype "passive"))
    )
    (net (code "14") (name "Net-(C13-Pad1)") (class "Default")
      (node (ref "C13") (pin "1") (pinfunction "1_1") (pintype "passive"))
      (node (ref "C8") (pin "2") (pinfunction "2_2") (pintype "passive"))
    )
    (net (code "15") (name "Net-(C15-Pad+)") (class "Default")
      (node (ref "C15") (pin "+") (pinfunction "+_+") (pintype "passive"))
      (node (ref "D2") (pin "C") (pinfunction "C_C") (pintype "passive"))
      (node (ref "D8") (pin "C") (pinfunction "C_C") (pintype "passive"))
      (node (ref "F2") (pin "2") (pinfunction "2_2") (pintype "passive"))
    )
    (net (code "16") (name "Net-(C17-Pad+)") (class "Default")
      (node (ref "C17") (pin "+") (pinfunction "+_+") (pintype "passive"))
      (node (ref "R45") (pin "1") (pinfunction "1_1") (pintype "passive"))
      (node (ref "R50") (pin "1") (pinfunction "1_1") (pintype "passive"))
      (node (ref "T1") (pin "E") (pinfunction "E_E") (pintype "passive"))
    )
    (net (code "17") (name "Net-(C19-Pad1)") (class "Default")
      (node (ref "C19") (pin "1") (pinfunction "1_1") (pintype "passive"))
      (node (ref "D24") (pin "C") (pinfunction "C_C") (pintype "passive"))
      (node (ref "D25") (pin "A") (pinfunction "A_A") (pintype "passive"))
      (node (ref "R52") (pin "1") (pinfunction "1_1") (pintype "passive"))
    )
    (net (code "18") (name "Net-(C20-Pad1)") (class "Default")
      (node (ref "C20") (pin "1") (pinfunction "1_1") (pintype "passive"))
      (node (ref "D22") (pin "A") (pinfunction "A_A") (pintype "passive"))
      (node (ref "D23") (pin "C") (pinfunction "C_C") (pintype "passive"))
      (node (ref "R53") (pin "1") (pinfunction "1_1") (pintype "passive"))
    )
    (net (code "19") (name "Net-(D3-PadA)") (class "Default")
      (node (ref "D3") (pin "A") (pinfunction "A_A") (pintype "passive"))
      (node (ref "D4") (pin "A") (pinfunction "A_A") (pintype "passive"))
      (node (ref "R25") (pin "2") (pinfunction "2_2") (pintype "passive"))
    )
    (net (code "20") (name "Net-(D7-PadC)") (class "Default")
      (node (ref "D7") (pin "C") (pinfunction "C_C") (pintype "passive"))
      (node (ref "F2") (pin "1") (pinfunction "1_1") (pintype "passive"))
      (node (ref "R26") (pin "1") (pinfunction "1_1") (pintype "passive"))
    )
    (net (code "21") (name "Net-(D9-PadA)") (class "Default")
      (node (ref "D9") (pin "A") (pinfunction "A_A") (pintype "passive"))
      (node (ref "Q13") (pin "S") (pinfunction "S_S") (pintype "passive"))
      (node (ref "Q14") (pin "S") (pinfunction "S_S") (pintype "passive"))
      (node (ref "Q15") (pin "S") (pinfunction "S_S") (pintype "passive"))
      (node (ref "R33") (pin "2") (pinfunction "2_2") (pintype "passive"))
      (node (ref "R44") (pin "2") (pinfunction "2_2") (pintype "passive"))
    )
    (net (code "22") (name "Net-(D9-PadC)") (class "Default")
      (node (ref "D9") (pin "C") (pinfunction "C_C") (pintype "passive"))
      (node (ref "R29") (pin "2") (pinfunction "2_2") (pintype "passive"))
      (node (ref "R30") (pin "2") (pinfunction "2_2") (pintype "passive"))
      (node (ref "R31") (pin "2") (pinfunction "2_2") (pintype "passive"))
      (node (ref "R33") (pin "1") (pinfunction "1_1") (pintype "passive"))
      (node (ref "R36") (pin "1") (pinfunction "1_1") (pintype "passive"))
    )
    (net (code "23") (name "Net-(D10-PadC)") (class "Default")
      (node (ref "D10") (pin "C") (pinfunction "C_C") (pintype "passive"))
      (node (ref "Q5") (pin "E") (pinfunction "E_E") (pintype "passive"))
      (node (ref "R20") (pin "1") (pinfunction "1_1") (pintype "passive"))
      (node (ref "R21") (pin "2") (pinfunction "2_2") (pintype "passive"))
    )
    (net (code "24") (name "Net-(D11-PadC)") (class "Default")
      (node (ref "D11") (pin "C") (pinfunction "C_C") (pintype "passive"))
      (node (ref "Q6") (pin "B") (pinfunction "B_B") (pintype "passive"))
      (node (ref "R24") (pin "1") (pinfunction "1_1") (pintype "passive"))
    )
    (net (code "25") (name "Net-(D12-PadC)") (class "Default")
      (node (ref "D12") (pin "C") (pinfunction "C_C") (pintype "passive"))
      (node (ref "IC2") (pin "6") (pinfunction "6_6") (pintype "passive"))
      (node (ref "R19") (pin "2") (pinfunction "2_2") (pintype "passive"))
      (node (ref "R5") (pin "2") (pinfunction "2_2") (pintype "passive"))
      (node (ref "R6") (pin "1") (pinfunction "1_1") (pintype "passive"))
    )
    (net (code "26") (name "Net-(D13-PadA)") (class "Default")
      (node (ref "D13") (pin "A") (pinfunction "A_A") (pintype "passive"))
      (node (ref "R18") (pin "2") (pinfunction "2_2") (pintype "passive"))
      (node (ref "R27") (pin "2") (pinfunction "2_2") (pintype "passive"))
      (node (ref "R28") (pin "2") (pinfunction "2_2") (pintype "passive"))
      (node (ref "R32") (pin "2") (pinfunction "2_2") (pintype "passive"))
      (node (ref "R34") (pin "1") (pinfunction "1_1") (pintype "passive"))
    )
    (net (code "27") (name "Net-(D13-PadC)") (class "Default")
      (node (ref "D13") (pin "C") (pinfunction "C_C") (pintype "passive"))
      (node (ref "Q10") (pin "S") (pinfunction "S_S") (pintype "passive"))
      (node (ref "Q11") (pin "S") (pinfunction "S_S") (pintype "passive"))
      (node (ref "Q12") (pin "S") (pinfunction "S_S") (pintype "passive"))
      (node (ref "R32") (pin "1") (pinfunction "1_1") (pintype "passive"))
      (node (ref "R45") (pin "2") (pinfunction "2_2") (pintype "passive"))
    )
    (net (code "28") (name "Net-(D20-PadC)") (class "Default")
      (node (ref "D20") (pin "C") (pinfunction "C_C") (pintype "passive"))
      (node (ref "D22") (pin "C") (pinfunction "C_C") (pintype "passive"))
      (node (ref "D25") (pin "C") (pinfunction "C_C") (pintype "passive"))
      (node (ref "R55") (pin "2") (pinfunction "2_2") (pintype "passive"))
      (node (ref "T3") (pin "B") (pinfunction "B_B") (pintype "passive"))
    )
    (net (code "29") (name "Net-(D21-PadA)") (class "Default")
      (node (ref "D21") (pin "A") (pinfunction "A_A") (pintype "passive"))
      (node (ref "D23") (pin "A") (pinfunction "A_A") (pintype "passive"))
      (node (ref "D24") (pin "A") (pinfunction "A_A") (pintype "passive"))
      (node (ref "R54") (pin "2") (pinfunction "2_2") (pintype "passive"))
      (node (ref "T4") (pin "B") (pinfunction "B_B") (pintype "passive"))
    )
    (net (code "30") (name "Net-(F3-Pad2A)") (class "Default")
      (node (ref "F3") (pin "2A") (pinfunction "2A_2A") (pintype "passive"))
      (node (ref "F5") (pin "2A") (pinfunction "2A_2A") (pintype "passive"))
      (node (ref "Q10") (pin "D") (pinfunction "D_D") (pintype "passive"))
      (node (ref "Q11") (pin "D") (pinfunction "D_D") (pintype "passive"))
      (node (ref "Q12") (pin "D") (pinfunction "D_D") (pintype "passive"))
    )
    (net (code "31") (name "Net-(F6-Pad2A)") (class "Default")
      (node (ref "F6") (pin "2A") (pinfunction "2A_2A") (pintype "passive"))
      (node (ref "F7") (pin "2A") (pinfunction "2A_2A") (pintype "passive"))
      (node (ref "Q13") (pin "D") (pinfunction "D_D") (pintype "passive"))
      (node (ref "Q14") (pin "D") (pinfunction "D_D") (pintype "passive"))
      (node (ref "Q15") (pin "D") (pinfunction "D_D") (pintype "passive"))
    )
    (net (code "32") (name "Net-(IC1-Pad4)") (class "Default")
      (node (ref "IC1") (pin "4") (pinfunction "4_4") (pintype "passive"))
      (node (ref "R4") (pin "2") (pinfunction "2_2") (pintype "passive"))
    )
    (net (code "33") (name "Net-(IC1-Pad12)") (class "Default")
      (node (ref "IC1") (pin "12") (pinfunction "12_12") (pintype "passive"))
      (node (ref "R8") (pin "1") (pinfunction "1_1") (pintype "passive"))
    )
    (net (code "34") (name "Net-(IC1-Pad13)") (class "Default")
      (node (ref "IC1") (pin "13") (pinfunction "13_13") (pintype "passive"))
      (node (ref "R7") (pin "1") (pinfunction "1_1") (pintype "passive"))
    )
    (net (code "35") (name "Net-(IC1-Pad14)") (class "Default")
      (node (ref "IC1") (pin "14") (pinfunction "14_14") (pintype "passive"))
      (node (ref "R23") (pin "2") (pinfunction "2_2") (pintype "passive"))
    )
    (net (code "36") (name "Net-(IC2-Pad1)") (class "Default")
      (node (ref "IC2") (pin "1") (pinfunction "1_1") (pintype "passive"))
      (node (ref "R9") (pin "2") (pinfunction "2_2") (pintype "passive"))
    )
    (net (code "37") (name "Net-(IC3-Pad3)") (class "Default")
      (node (ref "IC3") (pin "3") (pinfunction "3_3") (pintype "passive"))
      (node (ref "R14") (pin "1") (pinfunction "1_1") (pintype "passive"))
    )
    (net (code "38") (name "Net-(K1A-1)") (class "Default")
      (node (ref "D6") (pin "C") (pinfunction "C_C") (pintype "passive"))
      (node (ref "K1") (pin "A1") (pinfunction "1_A1") (pintype "passive"))
      (node (ref "R12") (pin "1") (pinfunction "1_1") (pintype "passive"))
    )
    (net (code "39") (name "Net-(K1A-2)") (class "Default")
      (node (ref "D6") (pin "A") (pinfunction "A_A") (pintype "passive"))
      (node (ref "K1") (pin "A2") (pinfunction "2_A2") (pintype "passive"))
      (node (ref "Q6") (pin "E") (pinfunction "E_E") (pintype "passive"))
    )
    (net (code "40") (name "Net-(K1B-PA)") (class "Default")
      (node (ref "C13") (pin "2") (pinfunction "2_2") (pintype "passive"))
      (node (ref "K1") (pin "11A") (pinfunction "PA_11A") (pintype "passive"))
      (node (ref "K1") (pin "11B") (pinfunction "PB_11B") (pintype "passive"))
      (node (ref "X1") (pin "3") (pinfunction "1_3") (pintype "passive"))
      (node (ref "X1") (pin "4") (pinfunction "1_4") (pintype "passive"))
    )
    (net (code "41") (name "Net-(K1B-SA)") (class "Default")
      (node (ref "C8") (pin "1") (pinfunction "1_1") (pintype "passive"))
      (node (ref "F4") (pin "1A") (pinfunction "1A_1A") (pintype "passive"))
      (node (ref "K1") (pin "14A") (pinfunction "SA_14A") (pintype "passive"))
      (node (ref "K1") (pin "14B") (pinfunction "SB_14B") (pintype "passive"))
      (node (ref "X9") (pin "1") (pinfunction "1_1") (pintype "passive"))
    )
    (net (code "42") (name "Net-(Q4-PadS)") (class "Default")
      (node (ref "Q4") (pin "S") (pinfunction "S_S") (pintype "passive"))
      (node (ref "R26") (pin "2") (pinfunction "2_2") (pintype "passive"))
    )
    (net (code "43") (name "Net-(Q5-PadB)") (class "Default")
      (node (ref "Q5") (pin "B") (pinfunction "B_B") (pintype "passive"))
      (node (ref "R19") (pin "1") (pinfunction "1_1") (pintype "passive"))
    )
    (net (code "44") (name "Net-(Q7-PadC)") (class "Default")
      (node (ref "Q7") (pin "C") (pinfunction "C_C") (pintype "passive"))
      (node (ref "R11") (pin "2") (pinfunction "2_2") (pintype "passive"))
    )
    (net (code "45") (name "Net-(Q8-PadB)") (class "Default")
      (node (ref "Q8") (pin "B") (pinfunction "B_B") (pintype "passive"))
      (node (ref "R6") (pin "2") (pinfunction "2_2") (pintype "passive"))
    )
    (net (code "46") (name "Net-(Q9-PadB)") (class "Default")
      (node (ref "Q9") (pin "B") (pinfunction "B_B") (pintype "passive"))
      (node (ref "R40") (pin "1") (pinfunction "1_1") (pintype "passive"))
    )
    (net (code "47") (name "Net-(Q10-PadG)") (class "Default")
      (node (ref "Q10") (pin "G") (pinfunction "G_G") (pintype "passive"))
      (node (ref "R18") (pin "1") (pinfunction "1_1") (pintype "passive"))
    )
    (net (code "48") (name "Net-(Q11-PadG)") (class "Default")
      (node (ref "Q11") (pin "G") (pinfunction "G_G") (pintype "passive"))
      (node (ref "R27") (pin "1") (pinfunction "1_1") (pintype "passive"))
    )
    (net (code "49") (name "Net-(Q12-PadG)") (class "Default")
      (node (ref "Q12") (pin "G") (pinfunction "G_G") (pintype "passive"))
      (node (ref "R28") (pin "1") (pinfunction "1_1") (pintype "passive"))
    )
    (net (code "50") (name "Net-(Q13-PadG)") (class "Default")
      (node (ref "Q13") (pin "G") (pinfunction "G_G") (pintype "passive"))
      (node (ref "R29") (pin "1") (pinfunction "1_1") (pintype "passive"))
    )
    (net (code "51") (name "Net-(Q14-PadG)") (class "Default")
      (node (ref "Q14") (pin "G") (pinfunction "G_G") (pintype "passive"))
      (node (ref "R30") (pin "1") (pinfunction "1_1") (pintype "passive"))
    )
    (net (code "52") (name "Net-(Q15-PadG)") (class "Default")
      (node (ref "Q15") (pin "G") (pinfunction "G_G") (pintype "passive"))
      (node (ref "R31") (pin "1") (pinfunction "1_1") (pintype "passive"))
    )
    (net (code "53") (name "Net-(Q18-PadB)") (class "Default")
      (node (ref "Q18") (pin "B") (pinfunction "B_B") (pintype "passive"))
      (node (ref "R41") (pin "2") (pinfunction "2_2") (pintype "passive"))
      (node (ref "R56") (pin "1") (pinfunction "1_1") (pintype "passive"))
    )
    (net (code "54") (name "Net-(Q18-PadC)") (class "Default")
      (node (ref "Q18") (pin "C") (pinfunction "C_C") (pintype "passive"))
      (node (ref "R38") (pin "1") (pinfunction "1_1") (pintype "passive"))
    )
    (net (code "55") (name "Net-(Q19-PadB)") (class "Default")
      (node (ref "Q19") (pin "B") (pinfunction "B_B") (pintype "passive"))
      (node (ref "R38") (pin "2") (pinfunction "2_2") (pintype "passive"))
      (node (ref "R43") (pin "1") (pinfunction "1_1") (pintype "passive"))
    )
    (net (code "56") (name "Net-(Q23-PadB)") (class "Default")
      (node (ref "Q23") (pin "B") (pinfunction "B_B") (pintype "passive"))
      (node (ref "R23") (pin "1") (pinfunction "1_1") (pintype "passive"))
    )
    (net (code "57") (name "Net-(Q24-PadB)") (class "Default")
      (node (ref "Q24") (pin "B") (pinfunction "B_B") (pintype "passive"))
      (node (ref "R46") (pin "1") (pinfunction "1_1") (pintype "passive"))
      (node (ref "R49") (pin "2") (pinfunction "2_2") (pintype "passive"))
    )
    (net (code "58") (name "Net-(Q24-PadC)") (class "Default")
      (node (ref "Q24") (pin "C") (pinfunction "C_C") (pintype "passive"))
      (node (ref "R56") (pin "2") (pinfunction "2_2") (pintype "passive"))
    )
    (net (code "59") (name "Net-(Q24-PadE)") (class "Default")
      (node (ref "Q24") (pin "E") (pinfunction "E_E") (pintype "passive"))
      (node (ref "R44") (pin "1") (pinfunction "1_1") (pintype "passive"))
      (node (ref "R46") (pin "2") (pinfunction "2_2") (pintype "passive"))
      (node (ref "T4") (pin "C") (pinfunction "C_C") (pintype "passive"))
    )
    (net (code "60") (name "Net-(R12-Pad2)") (class "Default")
      (node (ref "R12") (pin "2") (pinfunction "2_2") (pintype "passive"))
      (node (ref "R15") (pin "1") (pinfunction "1_1") (pintype "passive"))
    )
    (net (code "61") (name "Net-(R34-Pad2)") (class "Default")
      (node (ref "R34") (pin "2") (pinfunction "2_2") (pintype "passive"))
      (node (ref "T5") (pin "C") (pinfunction "C_C") (pintype "passive"))
    )
    (net (code "62") (name "Net-(R35-Pad1)") (class "Default")
      (node (ref "R35") (pin "1") (pinfunction "1_1") (pintype "passive"))
      (node (ref "T6") (pin "B") (pinfunction "B_B") (pintype "passive"))
    )
    (net (code "63") (name "Net-(R36-Pad2)") (class "Default")
      (node (ref "R36") (pin "2") (pinfunction "2_2") (pintype "passive"))
      (node (ref "T6") (pin "C") (pinfunction "C_C") (pintype "passive"))
    )
    (net (code "64") (name "Net-(R37-Pad1)") (class "Default")
      (node (ref "R37") (pin "1") (pinfunction "1_1") (pintype "passive"))
      (node (ref "T5") (pin "B") (pinfunction "B_B") (pintype "passive"))
    )
    (net (code "65") (name "Net-(R49-Pad1)") (class "Default")
      (node (ref "R49") (pin "1") (pinfunction "1_1") (pintype "passive"))
      (node (ref "T1") (pin "C") (pinfunction "C_C") (pintype "passive"))
    )
    (net (code "66") (name "Net-(R50-Pad2)") (class "Default")
      (node (ref "R50") (pin "2") (pinfunction "2_2") (pintype "passive"))
      (node (ref "R51") (pin "1") (pinfunction "1_1") (pintype "passive"))
      (node (ref "T1") (pin "B") (pinfunction "B_B") (pintype "passive"))
    )
    (net (code "67") (name "Net-(R51-Pad2)") (class "Default")
      (node (ref "R51") (pin "2") (pinfunction "2_2") (pintype "passive"))
      (node (ref "T3") (pin "C") (pinfunction "C_C") (pintype "passive"))
    )
    (net (code "68") (name "Net-(T3-PadE)") (class "Default")
      (node (ref "T3") (pin "E") (pinfunction "E_E") (pintype "passive"))
      (node (ref "T4") (pin "E") (pinfunction "E_E") (pintype "passive"))
    )
    (net (code "69") (name "Net-(T5-PadE)") (class "Default")
      (node (ref "T5") (pin "E") (pinfunction "E_E") (pintype "passive"))
      (node (ref "T6") (pin "E") (pinfunction "E_E") (pintype "passive"))
    )
    (net (code "70") (name "Net-(X1B-1)") (class "Default")
      (node (ref "X1") (pin "1") (pinfunction "1_1") (pintype "passive"))
      (node (ref "X1") (pin "2") (pinfunction "1_2") (pintype "passive"))
      (node (ref "X9") (pin "3") (pinfunction "1_3") (pintype "passive"))
      (node (ref "X9") (pin "4") (pinfunction "1_4") (pintype "passive"))
    )
    (net (code "71") (name "Net-(X2A-S)") (class "Default")
      (node (ref "D1") (pin "A") (pinfunction "A_A") (pintype "passive"))
      (node (ref "IC1") (pin "1") (pinfunction "1_1") (pintype "passive"))
      (node (ref "R1") (pin "2") (pinfunction "2_2") (pintype "passive"))
      (node (ref "X2") (pin "1") (pinfunction "S_1") (pintype "passive"))
    )
    (net (code "72") (name "Net-(X3A-S)") (class "Default")
      (node (ref "IC2") (pin "8") (pinfunction "8_8") (pintype "passive"))
      (node (ref "R13") (pin "1") (pinfunction "1_1") (pintype "passive"))
      (node (ref "R16") (pin "2") (pinfunction "2_2") (pintype "passive"))
      (node (ref "R20") (pin "2") (pinfunction "2_2") (pintype "passive"))
      (node (ref "R22") (pin "2") (pinfunction "2_2") (pintype "passive"))
      (node (ref "R5") (pin "1") (pinfunction "1_1") (pintype "passive"))
      (node (ref "X3") (pin "1") (pinfunction "S_1") (pintype "passive"))
      (node (ref "X5") (pin "3") (pinfunction "S_3") (pintype "passive"))
    )
    (net (code "73") (name "Net-(X3D-S)") (class "Default")
      (node (ref "R7") (pin "2") (pinfunction "2_2") (pintype "passive"))
      (node (ref "X3") (pin "4") (pinfunction "S_4") (pintype "passive"))
    )
    (net (code "74") (name "Net-(X3E-S)") (class "Default")
      (node (ref "R8") (pin "2") (pinfunction "2_2") (pintype "passive"))
      (node (ref "X3") (pin "5") (pinfunction "S_5") (pintype "passive"))
    )
    (net (code "75") (name "Net-(X4A-S)") (class "Default")
      (node (ref "IC2") (pin "3") (pinfunction "3_3") (pintype "passive"))
      (node (ref "IC3") (pin "4") (pinfunction "4_4") (pintype "passive"))
      (node (ref "X4") (pin "1") (pinfunction "S_1") (pintype "passive"))
    )
    (net (code "76") (name "Net-(X4B-S)") (class "Default")
      (node (ref "IC3") (pin "6") (pinfunction "6_6") (pintype "passive"))
      (node (ref "R9") (pin "1") (pinfunction "1_1") (pintype "passive"))
      (node (ref "X4") (pin "2") (pinfunction "S_2") (pintype "passive"))
    )
    (net (code "77") (name "Net-(X4C-S)") (class "Default")
      (node (ref "D3") (pin "C") (pinfunction "C_C") (pintype "passive"))
      (node (ref "D8") (pin "A") (pinfunction "A_A") (pintype "passive"))
      (node (ref "X4") (pin "3") (pinfunction "S_3") (pintype "passive"))
    )
    (net (code "78") (name "Net-(X4D-S)") (class "Default")
      (node (ref "D2") (pin "A") (pinfunction "A_A") (pintype "passive"))
      (node (ref "D4") (pin "C") (pinfunction "C_C") (pintype "passive"))
      (node (ref "X4") (pin "4") (pinfunction "S_4") (pintype "passive"))
    )
    (net (code "79") (name "Net-(X5A-S)") (class "Default")
      (node (ref "Q23") (pin "C") (pinfunction "C_C") (pintype "passive"))
      (node (ref "Q8") (pin "C") (pinfunction "C_C") (pintype "passive"))
      (node (ref "R22") (pin "1") (pinfunction "1_1") (pintype "passive"))
      (node (ref "X5") (pin "1") (pinfunction "S_1") (pintype "passive"))
    )
    (net (code "80") (name "Net-(X6A-S)") (class "Default")
      (node (ref "C14") (pin "1") (pinfunction "1_1") (pintype "passive"))
      (node (ref "R10") (pin "1") (pinfunction "1_1") (pintype "passive"))
      (node (ref "R39") (pin "1") (pinfunction "1_1") (pintype "passive"))
      (node (ref "X6") (pin "1") (pinfunction "S_1") (pintype "passive"))
    )
    (net (code "81") (name "Net-(X6C-S)") (class "Default")
      (node (ref "R39") (pin "2") (pinfunction "2_2") (pintype "passive"))
      (node (ref "R4") (pin "1") (pinfunction "1_1") (pintype "passive"))
      (node (ref "X6") (pin "3") (pinfunction "S_3") (pintype "passive"))
    )
    (net (code "82") (name "Net-(X7D-S)") (class "Default")
      (node (ref "C16") (pin "+") (pinfunction "+_+") (pintype "passive"))
      (node (ref "Q4") (pin "D") (pinfunction "D_D") (pintype "passive"))
      (node (ref "X7") (pin "4") (pinfunction "S_4") (pintype "passive"))
      (node (ref "X7") (pin "5") (pinfunction "S_5") (pintype "passive"))
    )
    (net (code "83") (name "Net-(X8A-S)") (class "Default")
      (node (ref "Q9") (pin "C") (pinfunction "C_C") (pintype "passive"))
      (node (ref "X8") (pin "1") (pinfunction "S_1") (pintype "passive"))
    )
    (net (code "84") (name "Net-(X8B-S)") (class "Default")
      (node (ref "R42") (pin "1") (pinfunction "1_1") (pintype "passive"))
      (node (ref "X8") (pin "2") (pinfunction "S_2") (pintype "passive"))
    )
    (net (code "85") (name "Net-(X8C-S)") (class "Default")
      (node (ref "D15") (pin "C") (pinfunction "C_C") (pintype "passive"))
      (node (ref "Q9") (pin "E") (pinfunction "E_E") (pintype "passive"))
      (node (ref "X8") (pin "3") (pinfunction "S_3") (pintype "passive"))
    )
    (net (code "86") (name "Net-(X9B-1)") (class "Default")
      (node (ref "F4") (pin "2A") (pinfunction "2A_2A") (pintype "passive"))
      (node (ref "X9") (pin "2") (pinfunction "1_2") (pintype "passive"))
    )
    (net (code "87") (name "Net-(X10A-S)") (class "Default")
      (node (ref "D15") (pin "A") (pinfunction "A_A") (pintype "passive"))
      (node (ref "Q18") (pin "E") (pinfunction "E_E") (pintype "passive"))
      (node (ref "R41") (pin "1") (pinfunction "1_1") (pintype "passive"))
      (node (ref "R47") (pin "2") (pinfunction "2_2") (pintype "passive"))
      (node (ref "X10") (pin "1") (pinfunction "S_1") (pintype "passive"))
    )
    (net (code "88") (name "Net-(X10B-S)") (class "Default")
      (node (ref "D14") (pin "C") (pinfunction "C_C") (pintype "passive"))
      (node (ref "Q19") (pin "E") (pinfunction "E_E") (pintype "passive"))
      (node (ref "R37") (pin "2") (pinfunction "2_2") (pintype "passive"))
      (node (ref "R40") (pin "2") (pinfunction "2_2") (pintype "passive"))
      (node (ref "R47") (pin "1") (pinfunction "1_1") (pintype "passive"))
      (node (ref "X10") (pin "2") (pinfunction "S_2") (pintype "passive"))
    )
    (net (code "89") (name "unconnected-(F3-Pad1A)") (class "Default")
      (node (ref "F3") (pin "1A") (pinfunction "1A_1A") (pintype "passive"))
    )
    (net (code "90") (name "unconnected-(F3-Pad1B)") (class "Default")
      (node (ref "F3") (pin "1B") (pinfunction "1B_1B") (pintype "passive"))
    )
    (net (code "91") (name "unconnected-(F3-Pad2B)") (class "Default")
      (node (ref "F3") (pin "2B") (pinfunction "2B_2B") (pintype "passive"))
    )
    (net (code "92") (name "unconnected-(F4-Pad1B)") (class "Default")
      (node (ref "F4") (pin "1B") (pinfunction "1B_1B") (pintype "passive"))
    )
    (net (code "93") (name "unconnected-(F4-Pad2B)") (class "Default")
      (node (ref "F4") (pin "2B") (pinfunction "2B_2B") (pintype "passive"))
    )
    (net (code "94") (name "unconnected-(F5-Pad1A)") (class "Default")
      (node (ref "F5") (pin "1A") (pinfunction "1A_1A") (pintype "passive"))
    )
    (net (code "95") (name "unconnected-(F5-Pad1B)") (class "Default")
      (node (ref "F5") (pin "1B") (pinfunction "1B_1B") (pintype "passive"))
    )
    (net (code "96") (name "unconnected-(F5-Pad2B)") (class "Default")
      (node (ref "F5") (pin "2B") (pinfunction "2B_2B") (pintype "passive"))
    )
    (net (code "97") (name "unconnected-(F6-Pad1A)") (class "Default")
      (node (ref "F6") (pin "1A") (pinfunction "1A_1A") (pintype "passive"))
    )
    (net (code "98") (name "unconnected-(F6-Pad1B)") (class "Default")
      (node (ref "F6") (pin "1B") (pinfunction "1B_1B") (pintype "passive"))
    )
    (net (code "99") (name "unconnected-(F6-Pad2B)") (class "Default")
      (node (ref "F6") (pin "2B") (pinfunction "2B_2B") (pintype "passive"))
    )
    (net (code "100") (name "unconnected-(F7-Pad1A)") (class "Default")
      (node (ref "F7") (pin "1A") (pinfunction "1A_1A") (pintype "passive"))
    )
    (net (code "101") (name "unconnected-(F7-Pad1B)") (class "Default")
      (node (ref "F7") (pin "1B") (pinfunction "1B_1B") (pintype "passive"))
    )
    (net (code "102") (name "unconnected-(F7-Pad2B)") (class "Default")
      (node (ref "F7") (pin "2B") (pinfunction "2B_2B") (pintype "passive"))
    )
    (net (code "103") (name "unconnected-(IC1-Pad2)") (class "Default")
      (node (ref "IC1") (pin "2") (pinfunction "2_2") (pintype "passive"))
    )
    (net (code "104") (name "unconnected-(IC1-Pad3)") (class "Default")
      (node (ref "IC1") (pin "3") (pinfunction "3_3") (pintype "passive"))
    )
    (net (code "105") (name "unconnected-(IC1-Pad5)") (class "Default")
      (node (ref "IC1") (pin "5") (pinfunction "5_5") (pintype "passive"))
    )
    (net (code "106") (name "unconnected-(IC1-Pad6)") (class "Default")
      (node (ref "IC1") (pin "6") (pinfunction "6_6") (pintype "passive"))
    )
    (net (code "107") (name "unconnected-(IC1-Pad11)") (class "Default")
      (node (ref "IC1") (pin "11") (pinfunction "11_11") (pintype "passive"))
    )
    (net (code "108") (name "unconnected-(IC1-Pad15)") (class "Default")
      (node (ref "IC1") (pin "15") (pinfunction "15_15") (pintype "passive"))
    )
    (net (code "109") (name "unconnected-(IC1-Pad16)") (class "Default")
      (node (ref "IC1") (pin "16") (pinfunction "16_16") (pintype "passive"))
    )
    (net (code "110") (name "unconnected-(IC1-Pad17)") (class "Default")
      (node (ref "IC1") (pin "17") (pinfunction "17_17") (pintype "passive"))
    )
    (net (code "111") (name "unconnected-(IC1-Pad18)") (class "Default")
      (node (ref "IC1") (pin "18") (pinfunction "18_18") (pintype "passive"))
    )
    (net (code "112") (name "unconnected-(IC1-Pad19)") (class "Default")
      (node (ref "IC1") (pin "19") (pinfunction "19_19") (pintype "passive"))
    )
    (net (code "113") (name "unconnected-(IC1-Pad21)") (class "Default")
      (node (ref "IC1") (pin "21") (pinfunction "21_21") (pintype "passive"))
    )
    (net (code "114") (name "unconnected-(IC1-Pad23)") (class "Default")
      (node (ref "IC1") (pin "23") (pinfunction "23_23") (pintype "passive"))
    )
    (net (code "115") (name "unconnected-(IC1-Pad24)") (class "Default")
      (node (ref "IC1") (pin "24") (pinfunction "24_24") (pintype "passive"))
    )
    (net (code "116") (name "unconnected-(IC1-Pad25)") (class "Default")
      (node (ref "IC1") (pin "25") (pinfunction "25_25") (pintype "passive"))
    )
    (net (code "117") (name "unconnected-(IC1-Pad26)") (class "Default")
      (node (ref "IC1") (pin "26") (pinfunction "26_26") (pintype "passive"))
    )
    (net (code "118") (name "unconnected-(IC1-Pad27)") (class "Default")
      (node (ref "IC1") (pin "27") (pinfunction "27_27") (pintype "passive"))
    )
    (net (code "119") (name "unconnected-(IC1-Pad28)") (class "Default")
      (node (ref "IC1") (pin "28") (pinfunction "28_28") (pintype "passive"))
    )
    (net (code "120") (name "unconnected-(IC2-Pad2)") (class "Default")
      (node (ref "IC2") (pin "2") (pinfunction "2_2") (pintype "passive"))
    )
    (net (code "121") (name "unconnected-(IC2-Pad4)") (class "Default")
      (node (ref "IC2") (pin "4") (pinfunction "4_4") (pintype "passive"))
    )
    (net (code "122") (name "unconnected-(IC2-Pad7)") (class "Default")
      (node (ref "IC2") (pin "7") (pinfunction "7_7") (pintype "passive"))
    )
    (net (code "123") (name "unconnected-(IC3-Pad2)") (class "Default")
      (node (ref "IC3") (pin "2") (pinfunction "2_2") (pintype "passive"))
    )
    (net (code "124") (name "unconnected-(IC3-Pad5)") (class "Default")
      (node (ref "IC3") (pin "5") (pinfunction "5_5") (pintype "passive"))
    )
    (net (code "125") (name "unconnected-(K1B-OA-Pad12A)") (class "Default")
      (node (ref "K1") (pin "12A") (pinfunction "OA_12A") (pintype "passive"))
    )
    (net (code "126") (name "unconnected-(K1B-OB-Pad12B)") (class "Default")
      (node (ref "K1") (pin "12B") (pinfunction "OB_12B") (pintype "passive"))
    )
    (net (code "127") (name "unconnected-(R52-Pad2)") (class "Default")
      (node (ref "R52") (pin "2") (pinfunction "2_2") (pintype "passive"))
    )
    (net (code "128") (name "unconnected-(R53-Pad2)") (class "Default")
      (node (ref "R53") (pin "2") (pinfunction "2_2") (pintype "passive"))
    )
  )
)
